# LEDDimmerSimple.net
KiCad netlist of a schematic drawn in EAGLE
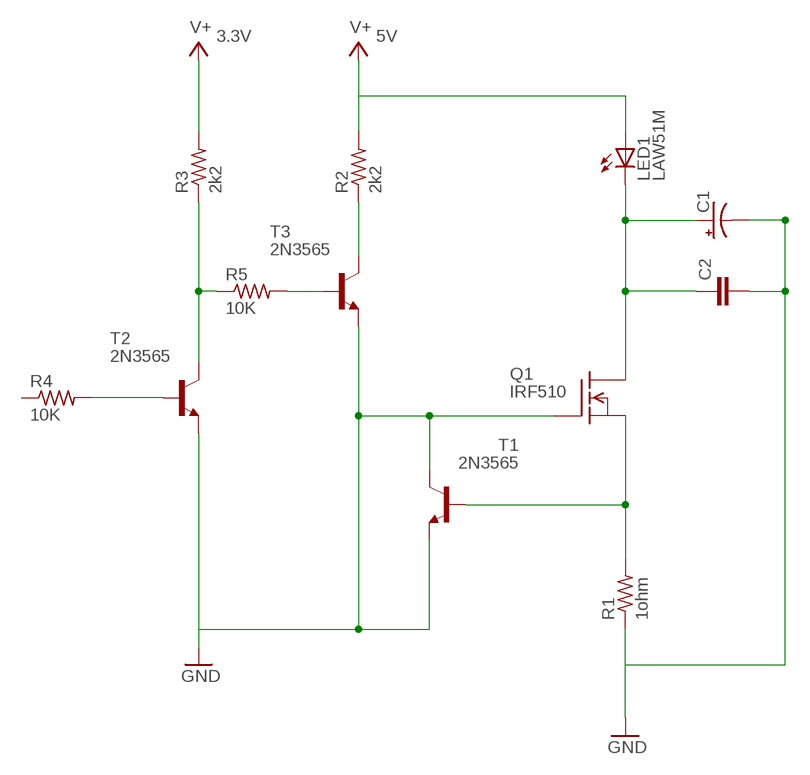
[diagram p0: schematic, sheet 1]

(export (version "E")
  (design (tool "Eeschema 10.0.6"))
  (components
    (comp (ref "C1")
      (value "CPOL-USE1.8-4")
      (footprint "eagle-import:E1,8-4")
      (libsource (lib "eagle-import") (part "CPOL-USE1.8-4"))
    )
    (comp (ref "C2")
      (value "C-EU025-030X050")
      (footprint "eagle-import:C025-030X050")
      (libsource (lib "eagle-import") (part "C-EU025-030X050"))
    )
    (comp (ref "LED1")
      (value "LAW51M")
      (footprint "eagle-import:W51")
      (libsource (lib "eagle-import") (part "W51MLA"))
    )
    (comp (ref "Q1")
      (value "IRF510")
      (footprint "eagle-import:TO220")
      (libsource (lib "eagle-import") (part "IRF510"))
    )
    (comp (ref "R1")
      (value "1ohm")
      (footprint "eagle-import:P0613V")
      (libsource (lib "eagle-import") (part "R-US_0613/5V"))
    )
    (comp (ref "R2")
      (value "2k2")
      (footprint "eagle-import:0207_7")
      (libsource (lib "eagle-import") (part "R-US_0207/7"))
    )
    (comp (ref "R3")
      (value "2k2")
      (footprint "eagle-import:0207_7")
      (libsource (lib "eagle-import") (part "R-US_0207/7"))
    )
    (comp (ref "R4")
      (value "10K")
      (footprint "eagle-import:0207_7")
      (libsource (lib "eagle-import") (part "R-US_0207/7"))
    )
    (comp (ref "R5")
      (value "10K")
      (footprint "eagle-import:0207_7")
      (libsource (lib "eagle-import") (part "R-US_0207/7"))
    )
    (comp (ref "T1")
      (value "2N3565")
      (footprint "eagle-import:TO92")
      (libsource (lib "eagle-import") (part "2N3565"))
    )
    (comp (ref "T2")
      (value "2N3565")
      (footprint "eagle-import:TO92")
      (libsource (lib "eagle-import") (part "2N3565"))
    )
    (comp (ref "T3")
      (value "2N3565")
      (footprint "eagle-import:TO92")
      (libsource (lib "eagle-import") (part "2N3565"))
    )
  )
  (nets
    (net (code "1") (name "GND") (class "Default")
      (node (ref "C1") (pin "-") (pinfunction "-_-") (pintype "passive"))
      (node (ref "C2") (pin "2") (pinfunction "2_2") (pintype "passive"))
      (node (ref "Q1") (pin "1") (pinfunction "G_1") (pintype "passive"))
      (node (ref "R1") (pin "1") (pinfunction "1_1") (pintype "passive"))
      (node (ref "T1") (pin "1") (pinfunction "C_1") (pintype "passive"))
      (node (ref "T1") (pin "3") (pinfunction "E_3") (pintype "passive"))
      (node (ref "T2") (pin "3") (pinfunction "E_3") (pintype "passive"))
      (node (ref "T3") (pin "3") (pinfunction "E_3") (pintype "passive"))
    )
    (net (code "2") (name "Net-(Q1-D)") (class "Default")
      (node (ref "C1") (pin "+") (pinfunction "+_+") (pintype "passive"))
      (node (ref "C2") (pin "1") (pinfunction "1_1") (pintype "passive"))
      (node (ref "LED1") (pin "C") (pinfunction "C_C") (pintype "passive"))
      (node (ref "Q1") (pin "2") (pinfunction "D_2") (pintype "passive"))
    )
    (net (code "3") (name "Net-(Q1-S)") (class "Default")
      (node (ref "Q1") (pin "3") (pinfunction "S_3") (pintype "passive"))
      (node (ref "R1") (pin "2") (pinfunction "2_2") (pintype "passive"))
      (node (ref "T1") (pin "2") (pinfunction "B_2") (pintype "passive"))
    )
    (net (code "4") (name "Net-(T2-B)") (class "Default")
      (node (ref "R4") (pin "2") (pinfunction "2_2") (pintype "passive"))
      (node (ref "T2") (pin "2") (pinfunction "B_2") (pintype "passive"))
    )
    (net (code "5") (name "Net-(T2-C)") (class "Default")
      (node (ref "R3") (pin "1") (pinfunction "1_1") (pintype "passive"))
      (node (ref "R5") (pin "1") (pinfunction "1_1") (pintype "passive"))
      (node (ref "T2") (pin "1") (pinfunction "C_1") (pintype "passive"))
    )
    (net (code "6") (name "Net-(T3-B)") (class "Default")
      (node (ref "R5") (pin "2") (pinfunction "2_2") (pintype "passive"))
      (node (ref "T3") (pin "2") (pinfunction "B_2") (pintype "passive"))
    )
    (net (code "7") (name "Net-(T3-C)") (class "Default")
      (node (ref "R2") (pin "1") (pinfunction "1_1") (pintype "passive"))
      (node (ref "T3") (pin "1") (pinfunction "C_1") (pintype "passive"))
    )
    (net (code "8") (name "V+") (class "Default")
      (node (ref "LED1") (pin "A") (pinfunction "A_A") (pintype "passive"))
      (node (ref "R2") (pin "2") (pinfunction "2_2") (pintype "passive"))
      (node (ref "R3") (pin "2") (pinfunction "2_2") (pintype "passive"))
    )
    (net (code "9") (name "unconnected-(R4-Pad1)") (class "Default")
      (node (ref "R4") (pin "1") (pinfunction "1_1") (pintype "passive"))
    )
  )
)
